# Arduino_Nano_Countdown_Timer_7-seg_CC.net
KiCad netlist of a schematic drawn in EAGLE
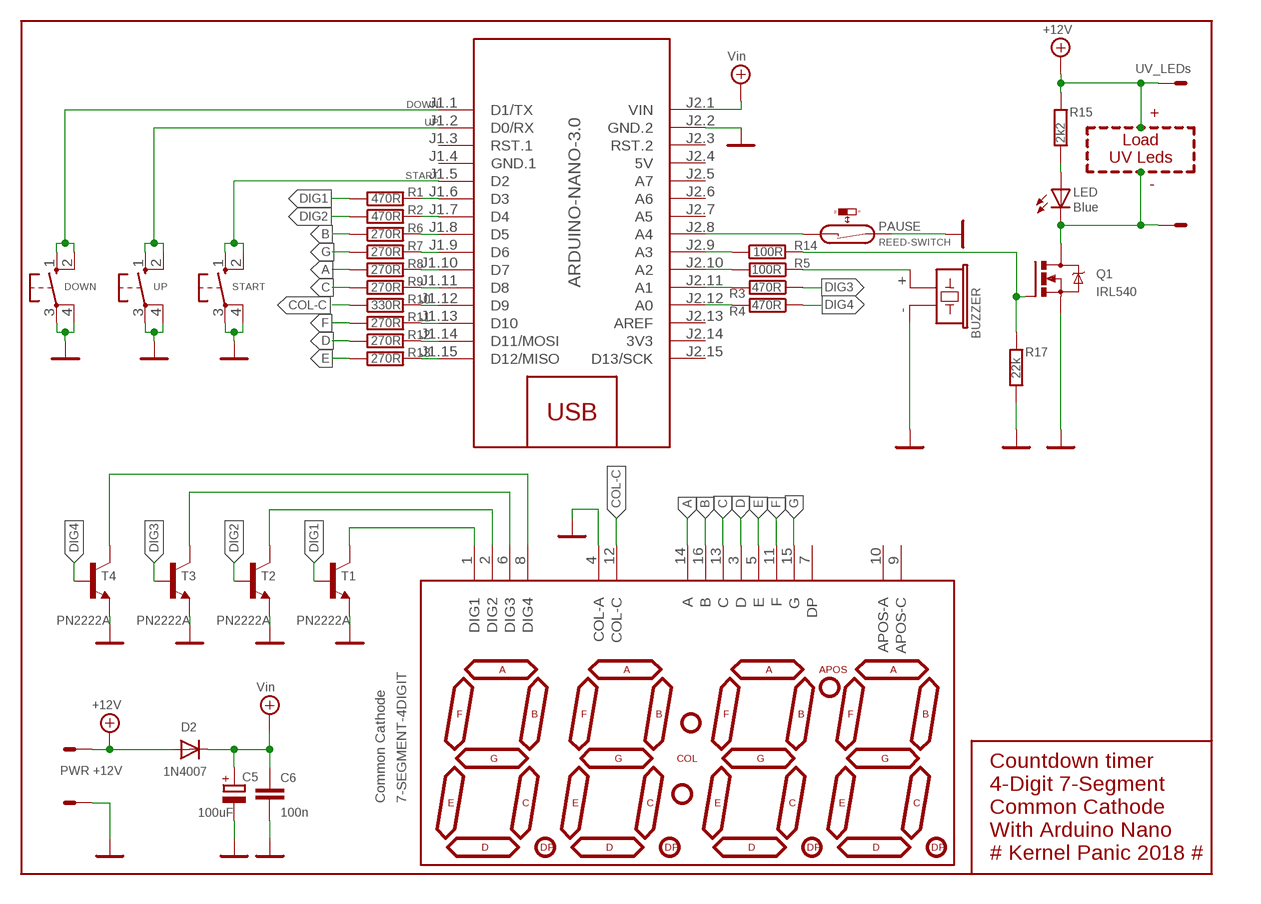
[diagram p0: schematic, sheet 1]

(export (version "E")
  (design (tool "Eeschema 10.0.6"))
  (components
    (comp (ref "BUZZER")
      (value "F/CM12P")
      (footprint "eagle-import:F_CM12P")
      (libsource (lib "eagle-import") (part "F/CM12P"))
    )
    (comp (ref "C5")
      (value "100uF")
      (footprint "eagle-import:E5-6.5")
      (libsource (lib "eagle-import") (part "CAPACITOR_POLE5-6.5"))
    )
    (comp (ref "C6")
      (value "100n")
      (footprint "eagle-import:C050-025X075")
      (libsource (lib "eagle-import") (part "CAPACITOR050-025X075"))
    )
    (comp (ref "D2")
      (value "1N4007")
      (footprint "eagle-import:DO41-10")
      (libsource (lib "eagle-import") (part "DIODE1N4004"))
    )
    (comp (ref "DOWN")
      (value "SWITCHE6K")
      (footprint "eagle-import:DTE6K")
      (libsource (lib "eagle-import") (part "SWITCHE6K"))
    )
    (comp (ref "LED")
      (value "Blue")
      (footprint "eagle-import:LED3MM")
      (libsource (lib "eagle-import") (part "LED3MM"))
    )
    (comp (ref "LED2")
      (value "7-SEGMENT-4DIGIT")
      (footprint "eagle-import:7-SEGMENT-4DIGIT")
      (libsource (lib "eagle-import") (part "7-SEGMENT-4DIGIT"))
    )
    (comp (ref "LOAD")
      (value "UV_LEDs")
      (footprint "eagle-import:22-23-2021")
      (fields (field (name "MF") "MOLEX") (field (name "MPN") "22-23-2021"))
      (libsource (lib "eagle-import") (part "22-23-2021"))
    )
    (comp (ref "M2")
      (value "ARDUINO-NANO-3.0")
      (footprint "eagle-import:ARDUINO-NANO-3.0")
      (libsource (lib "eagle-import") (part "ARDUINO-NANO-3.0"))
    )
    (comp (ref "PAUSE")
      (value "REED-SWITCH")
      (footprint "eagle-import:2PIN_HEADER")
      (libsource (lib "eagle-import") (part "REED-SWITCH-2PIN"))
    )
    (comp (ref "PWR")
      (value "PWR +12V")
      (footprint "eagle-import:22-23-2021")
      (fields (field (name "MF") "MOLEX") (field (name "MPN") "22-23-2021"))
      (libsource (lib "eagle-import") (part "22-23-2021"))
    )
    (comp (ref "Q1")
      (value "IRL540")
      (footprint "eagle-import:TO220BV")
      (libsource (lib "eagle-import") (part "IRF540"))
    )
    (comp (ref "R1")
      (value "470R")
      (footprint "eagle-import:R0805")
      (libsource (lib "eagle-import") (part "RESISTORR0805"))
    )
    (comp (ref "R2")
      (value "470R")
      (footprint "eagle-import:R0805")
      (libsource (lib "eagle-import") (part "RESISTORR0805"))
    )
    (comp (ref "R3")
      (value "470R")
      (footprint "eagle-import:R0805")
      (libsource (lib "eagle-import") (part "RESISTORR0805"))
    )
    (comp (ref "R4")
      (value "470R")
      (footprint "eagle-import:R0805")
      (libsource (lib "eagle-import") (part "RESISTORR0805"))
    )
    (comp (ref "R5")
      (value "100R")
      (footprint "eagle-import:R0805")
      (libsource (lib "eagle-import") (part "RESISTORR0805"))
    )
    (comp (ref "R6")
      (value "270R")
      (footprint "eagle-import:R0805")
      (libsource (lib "eagle-import") (part "RESISTORR0805"))
    )
    (comp (ref "R7")
      (value "270R")
      (footprint "eagle-import:R0805")
      (libsource (lib "eagle-import") (part "RESISTORR0805"))
    )
    (comp (ref "R8")
      (value "270R")
      (footprint "eagle-import:R0805")
      (libsource (lib "eagle-import") (part "RESISTORR0805"))
    )
    (comp (ref "R9")
      (value "270R")
      (footprint "eagle-import:R0805")
      (libsource (lib "eagle-import") (part "RESISTORR0805"))
    )
    (comp (ref "R10")
      (value "330R")
      (footprint "eagle-import:R0805")
      (libsource (lib "eagle-import") (part "RESISTORR0805"))
    )
    (comp (ref "R11")
      (value "270R")
      (footprint "eagle-import:R0805")
      (libsource (lib "eagle-import") (part "RESISTORR0805"))
    )
    (comp (ref "R12")
      (value "270R")
      (footprint "eagle-import:R0805")
      (libsource (lib "eagle-import") (part "RESISTORR0805"))
    )
    (comp (ref "R13")
      (value "270R")
      (footprint "eagle-import:R0805")
      (libsource (lib "eagle-import") (part "RESISTORR0805"))
    )
    (comp (ref "R14")
      (value "100R")
      (footprint "eagle-import:0207_10-8")
      (libsource (lib "eagle-import") (part "RESISTOR0207/10-OCTAGON"))
    )
    (comp (ref "R15")
      (value "2k2")
      (footprint "eagle-import:R0805")
      (libsource (lib "eagle-import") (part "RESISTORR0805"))
    )
    (comp (ref "R17")
      (value "22k")
      (footprint "eagle-import:R0805")
      (libsource (lib "eagle-import") (part "RESISTORR0805"))
    )
    (comp (ref "START")
      (value "SWITCHE6K")
      (footprint "eagle-import:DTE6K")
      (libsource (lib "eagle-import") (part "SWITCHE6K"))
    )
    (comp (ref "T1")
      (value "PN2222A")
      (footprint "eagle-import:TO92-EBC-OVAL")
      (libsource (lib "eagle-import") (part "2N2222"))
    )
    (comp (ref "T2")
      (value "PN2222A")
      (footprint "eagle-import:TO92-EBC-OVAL")
      (libsource (lib "eagle-import") (part "2N2222"))
    )
    (comp (ref "T3")
      (value "PN2222A")
      (footprint "eagle-import:TO92-EBC-OVAL")
      (libsource (lib "eagle-import") (part "2N2222"))
    )
    (comp (ref "T4")
      (value "PN2222A")
      (footprint "eagle-import:TO92-EBC-OVAL")
      (libsource (lib "eagle-import") (part "2N2222"))
    )
    (comp (ref "UP")
      (value "SWITCHE6K")
      (footprint "eagle-import:DTE6K")
      (libsource (lib "eagle-import") (part "SWITCHE6K"))
    )
  )
  (nets
    (net (code "1") (name "+12V") (class "Default")
      (node (ref "D2") (pin "A") (pinfunction "A_A") (pintype "passive"))
      (node (ref "LOAD") (pin "1") (pinfunction "S_1") (pintype "passive"))
      (node (ref "PWR") (pin "2") (pinfunction "S_2") (pintype "passive"))
      (node (ref "R15") (pin "1") (pinfunction "1_1") (pintype "passive"))
    )
    (net (code "2") (name "/3V3") (class "Default")
      (node (ref "M2") (pin "J2.14") (pinfunction "3V3_J2.14") (pintype "power_in"))
    )
    (net (code "3") (name "/5V") (class "Default")
      (node (ref "M2") (pin "J2.4") (pinfunction "5V_J2.4") (pintype "power_in"))
    )
    (net (code "4") (name "/DOWN") (class "Default")
      (node (ref "DOWN") (pin "1") (pinfunction "S_1") (pintype "passive"))
      (node (ref "DOWN") (pin "2") (pinfunction "S_2") (pintype "passive"))
      (node (ref "M2") (pin "J1.1") (pinfunction "D1/TX_J1.1") (pintype "bidirectional"))
    )
    (net (code "5") (name "/GND.1") (class "Default")
      (node (ref "M2") (pin "J1.4") (pinfunction "GND.1_J1.4") (pintype "power_in"))
    )
    (net (code "6") (name "/START") (class "Default")
      (node (ref "M2") (pin "J1.5") (pinfunction "D2_J1.5") (pintype "bidirectional"))
      (node (ref "START") (pin "1") (pinfunction "S_1") (pintype "passive"))
      (node (ref "START") (pin "2") (pinfunction "S_2") (pintype "passive"))
    )
    (net (code "7") (name "/UP") (class "Default")
      (node (ref "M2") (pin "J1.2") (pinfunction "D0/RX_J1.2") (pintype "bidirectional"))
      (node (ref "UP") (pin "1") (pinfunction "S_1") (pintype "passive"))
      (node (ref "UP") (pin "2") (pinfunction "S_2") (pintype "passive"))
    )
    (net (code "8") (name "A") (class "Default")
      (node (ref "LED2") (pin "14") (pinfunction "A_14") (pintype "bidirectional"))
      (node (ref "R8") (pin "1") (pinfunction "1_1") (pintype "passive"))
    )
    (net (code "9") (name "B") (class "Default")
      (node (ref "LED2") (pin "16") (pinfunction "B_16") (pintype "bidirectional"))
      (node (ref "R6") (pin "1") (pinfunction "1_1") (pintype "passive"))
    )
    (net (code "10") (name "C") (class "Default")
      (node (ref "LED2") (pin "13") (pinfunction "C_13") (pintype "bidirectional"))
      (node (ref "R9") (pin "1") (pinfunction "1_1") (pintype "passive"))
    )
    (net (code "11") (name "COL-C") (class "Default")
      (node (ref "LED2") (pin "12") (pinfunction "COL-C_12") (pintype "bidirectional"))
      (node (ref "R10") (pin "1") (pinfunction "1_1") (pintype "passive"))
    )
    (net (code "12") (name "D") (class "Default")
      (node (ref "LED2") (pin "3") (pinfunction "D_3") (pintype "bidirectional"))
      (node (ref "R12") (pin "1") (pinfunction "1_1") (pintype "passive"))
    )
    (net (code "13") (name "DIG1") (class "Default")
      (node (ref "R1") (pin "1") (pinfunction "1_1") (pintype "passive"))
      (node (ref "T1") (pin "B") (pinfunction "B_B") (pintype "passive"))
    )
    (net (code "14") (name "DIG2") (class "Default")
      (node (ref "R2") (pin "1") (pinfunction "1_1") (pintype "passive"))
      (node (ref "T2") (pin "B") (pinfunction "B_B") (pintype "passive"))
    )
    (net (code "15") (name "DIG3") (class "Default")
      (node (ref "R3") (pin "1") (pinfunction "1_1") (pintype "passive"))
      (node (ref "T3") (pin "B") (pinfunction "B_B") (pintype "passive"))
    )
    (net (code "16") (name "DIG4") (class "Default")
      (node (ref "R4") (pin "1") (pinfunction "1_1") (pintype "passive"))
      (node (ref "T4") (pin "B") (pinfunction "B_B") (pintype "passive"))
    )
    (net (code "17") (name "E") (class "Default")
      (node (ref "LED2") (pin "5") (pinfunction "E_5") (pintype "bidirectional"))
      (node (ref "R13") (pin "1") (pinfunction "1_1") (pintype "passive"))
    )
    (net (code "18") (name "F") (class "Default")
      (node (ref "LED2") (pin "11") (pinfunction "F_11") (pintype "bidirectional"))
      (node (ref "R11") (pin "1") (pinfunction "1_1") (pintype "passive"))
    )
    (net (code "19") (name "G") (class "Default")
      (node (ref "LED2") (pin "15") (pinfunction "G_15") (pintype "bidirectional"))
      (node (ref "R7") (pin "1") (pinfunction "1_1") (pintype "passive"))
    )
    (net (code "20") (name "GND") (class "Default")
      (node (ref "BUZZER") (pin "-") (pinfunction "2_-") (pintype "passive"))
      (node (ref "C5") (pin "-") (pinfunction "-_-") (pintype "passive"))
      (node (ref "C6") (pin "2") (pinfunction "2_2") (pintype "passive"))
      (node (ref "DOWN") (pin "3") (pinfunction "P_3") (pintype "passive"))
      (node (ref "DOWN") (pin "4") (pinfunction "P_4") (pintype "passive"))
      (node (ref "LED2") (pin "4") (pinfunction "COL-A_4") (pintype "bidirectional"))
      (node (ref "M2") (pin "J2.2") (pinfunction "GND.2_J2.2") (pintype "power_in"))
      (node (ref "PAUSE") (pin "2") (pinfunction "2_2") (pintype "passive"))
      (node (ref "PWR") (pin "1") (pinfunction "S_1") (pintype "passive"))
      (node (ref "Q1") (pin "S") (pinfunction "S_S") (pintype "passive"))
      (node (ref "R17") (pin "2") (pinfunction "2_2") (pintype "passive"))
      (node (ref "START") (pin "3") (pinfunction "P_3") (pintype "passive"))
      (node (ref "START") (pin "4") (pinfunction "P_4") (pintype "passive"))
      (node (ref "T1") (pin "E") (pinfunction "E_E") (pintype "passive"))
      (node (ref "T2") (pin "E") (pinfunction "E_E") (pintype "passive"))
      (node (ref "T3") (pin "E") (pinfunction "E_E") (pintype "passive"))
      (node (ref "T4") (pin "E") (pinfunction "E_E") (pintype "passive"))
      (node (ref "UP") (pin "3") (pinfunction "P_3") (pintype "passive"))
      (node (ref "UP") (pin "4") (pinfunction "P_4") (pintype "passive"))
    )
    (net (code "21") (name "Net-(BUZZER-1)") (class "Default")
      (node (ref "BUZZER") (pin "+") (pinfunction "1_+") (pintype "passive"))
      (node (ref "R5") (pin "1") (pinfunction "1_1") (pintype "passive"))
    )
    (net (code "22") (name "Net-(LED-C)") (class "Default")
      (node (ref "LED") (pin "K") (pinfunction "C_K") (pintype "passive"))
      (node (ref "LOAD") (pin "2") (pinfunction "S_2") (pintype "passive"))
      (node (ref "Q1") (pin "D") (pinfunction "D_D") (pintype "passive"))
    )
    (net (code "23") (name "Net-(LED-PadA)") (class "Default")
      (node (ref "LED") (pin "A") (pinfunction "A_A") (pintype "passive"))
      (node (ref "R15") (pin "2") (pinfunction "2_2") (pintype "passive"))
    )
    (net (code "24") (name "Net-(LED2-DIG1)") (class "Default")
      (node (ref "LED2") (pin "1") (pinfunction "DIG1_1") (pintype "bidirectional"))
      (node (ref "T1") (pin "C") (pinfunction "C_C") (pintype "passive"))
    )
    (net (code "25") (name "Net-(LED2-DIG2)") (class "Default")
      (node (ref "LED2") (pin "2") (pinfunction "DIG2_2") (pintype "bidirectional"))
      (node (ref "T2") (pin "C") (pinfunction "C_C") (pintype "passive"))
    )
    (net (code "26") (name "Net-(LED2-DIG3)") (class "Default")
      (node (ref "LED2") (pin "6") (pinfunction "DIG3_6") (pintype "bidirectional"))
      (node (ref "T3") (pin "C") (pinfunction "C_C") (pintype "passive"))
    )
    (net (code "27") (name "Net-(LED2-DIG4)") (class "Default")
      (node (ref "LED2") (pin "8") (pinfunction "DIG4_8") (pintype "bidirectional"))
      (node (ref "T4") (pin "C") (pinfunction "C_C") (pintype "passive"))
    )
    (net (code "28") (name "Net-(M2-A0)") (class "Default")
      (node (ref "M2") (pin "J2.12") (pinfunction "A0_J2.12") (pintype "bidirectional"))
      (node (ref "R4") (pin "2") (pinfunction "2_2") (pintype "passive"))
    )
    (net (code "29") (name "Net-(M2-A1)") (class "Default")
      (node (ref "M2") (pin "J2.11") (pinfunction "A1_J2.11") (pintype "bidirectional"))
      (node (ref "R3") (pin "2") (pinfunction "2_2") (pintype "passive"))
    )
    (net (code "30") (name "Net-(M2-A2)") (class "Default")
      (node (ref "M2") (pin "J2.10") (pinfunction "A2_J2.10") (pintype "bidirectional"))
      (node (ref "R5") (pin "2") (pinfunction "2_2") (pintype "passive"))
    )
    (net (code "31") (name "Net-(M2-A3)") (class "Default")
      (node (ref "M2") (pin "J2.9") (pinfunction "A3_J2.9") (pintype "bidirectional"))
      (node (ref "R14") (pin "1") (pinfunction "1_1") (pintype "passive"))
    )
    (net (code "32") (name "Net-(M2-A4)") (class "Default")
      (node (ref "M2") (pin "J2.8") (pinfunction "A4_J2.8") (pintype "bidirectional"))
      (node (ref "PAUSE") (pin "1") (pinfunction "1_1") (pintype "passive"))
    )
    (net (code "33") (name "Net-(M2-D3)") (class "Default")
      (node (ref "M2") (pin "J1.6") (pinfunction "D3_J1.6") (pintype "bidirectional"))
      (node (ref "R1") (pin "2") (pinfunction "2_2") (pintype "passive"))
    )
    (net (code "34") (name "Net-(M2-D4)") (class "Default")
      (node (ref "M2") (pin "J1.7") (pinfunction "D4_J1.7") (pintype "bidirectional"))
      (node (ref "R2") (pin "2") (pinfunction "2_2") (pintype "passive"))
    )
    (net (code "35") (name "Net-(M2-D5)") (class "Default")
      (node (ref "M2") (pin "J1.8") (pinfunction "D5_J1.8") (pintype "bidirectional"))
      (node (ref "R6") (pin "2") (pinfunction "2_2") (pintype "passive"))
    )
    (net (code "36") (name "Net-(M2-D6)") (class "Default")
      (node (ref "M2") (pin "J1.9") (pinfunction "D6_J1.9") (pintype "bidirectional"))
      (node (ref "R7") (pin "2") (pinfunction "2_2") (pintype "passive"))
    )
    (net (code "37") (name "Net-(M2-D7)") (class "Default")
      (node (ref "M2") (pin "J1.10") (pinfunction "D7_J1.10") (pintype "bidirectional"))
      (node (ref "R8") (pin "2") (pinfunction "2_2") (pintype "passive"))
    )
    (net (code "38") (name "Net-(M2-D8)") (class "Default")
      (node (ref "M2") (pin "J1.11") (pinfunction "D8_J1.11") (pintype "bidirectional"))
      (node (ref "R9") (pin "2") (pinfunction "2_2") (pintype "passive"))
    )
    (net (code "39") (name "Net-(M2-D9)") (class "Default")
      (node (ref "M2") (pin "J1.12") (pinfunction "D9_J1.12") (pintype "bidirectional"))
      (node (ref "R10") (pin "2") (pinfunction "2_2") (pintype "passive"))
    )
    (net (code "40") (name "Net-(M2-D10)") (class "Default")
      (node (ref "M2") (pin "J1.13") (pinfunction "D10_J1.13") (pintype "bidirectional"))
      (node (ref "R11") (pin "2") (pinfunction "2_2") (pintype "passive"))
    )
    (net (code "41") (name "Net-(M2-D11{slash}MOSI)") (class "Default")
      (node (ref "M2") (pin "J1.14") (pinfunction "D11/MOSI_J1.14") (pintype "bidirectional"))
      (node (ref "R12") (pin "2") (pinfunction "2_2") (pintype "passive"))
    )
    (net (code "42") (name "Net-(M2-D12{slash}MISO)") (class "Default")
      (node (ref "M2") (pin "J1.15") (pinfunction "D12/MISO_J1.15") (pintype "bidirectional"))
      (node (ref "R13") (pin "2") (pinfunction "2_2") (pintype "passive"))
    )
    (net (code "43") (name "Net-(Q1-PadG)") (class "Default")
      (node (ref "Q1") (pin "G") (pinfunction "G_G") (pintype "passive"))
      (node (ref "R14") (pin "2") (pinfunction "2_2") (pintype "passive"))
      (node (ref "R17") (pin "1") (pinfunction "1_1") (pintype "passive"))
    )
    (net (code "44") (name "Vin") (class "Default")
      (node (ref "C5") (pin "+") (pinfunction "+_+") (pintype "passive"))
      (node (ref "C6") (pin "1") (pinfunction "1_1") (pintype "passive"))
      (node (ref "D2") (pin "C") (pinfunction "C_C") (pintype "passive"))
      (node (ref "M2") (pin "J2.1") (pinfunction "VIN_J2.1") (pintype "power_in"))
    )
    (net (code "45") (name "unconnected-(LED2-APOS-A-Pad10)") (class "Default")
      (node (ref "LED2") (pin "10") (pinfunction "APOS-A_10") (pintype "bidirectional"))
    )
    (net (code "46") (name "unconnected-(LED2-APOS-C-Pad9)") (class "Default")
      (node (ref "LED2") (pin "9") (pinfunction "APOS-C_9") (pintype "bidirectional"))
    )
    (net (code "47") (name "unconnected-(LED2-DP-Pad7)") (class "Default")
      (node (ref "LED2") (pin "7") (pinfunction "DP_7") (pintype "bidirectional"))
    )
    (net (code "48") (name "unconnected-(M2-A5-PadJ2.7)") (class "Default")
      (node (ref "M2") (pin "J2.7") (pinfunction "A5_J2.7") (pintype "bidirectional"))
    )
    (net (code "49") (name "unconnected-(M2-A6-PadJ2.6)") (class "Default")
      (node (ref "M2") (pin "J2.6") (pinfunction "A6_J2.6") (pintype "bidirectional"))
    )
    (net (code "50") (name "unconnected-(M2-A7-PadJ2.5)") (class "Default")
      (node (ref "M2") (pin "J2.5") (pinfunction "A7_J2.5") (pintype "bidirectional"))
    )
    (net (code "51") (name "unconnected-(M2-AREF-PadJ2.13)") (class "Default")
      (node (ref "M2") (pin "J2.13") (pinfunction "AREF_J2.13") (pintype "bidirectional"))
    )
    (net (code "52") (name "unconnected-(M2-D13{slash}SCK-PadJ2.15)") (class "Default")
      (node (ref "M2") (pin "J2.15") (pinfunction "D13/SCK_J2.15") (pintype "bidirectional"))
    )
    (net (code "53") (name "unconnected-(M2-RST.1-PadJ1.3)") (class "Default")
      (node (ref "M2") (pin "J1.3") (pinfunction "RST.1_J1.3") (pintype "bidirectional"))
    )
    (net (code "54") (name "unconnected-(M2-RST.2-PadJ2.3)") (class "Default")
      (node (ref "M2") (pin "J2.3") (pinfunction "RST.2_J2.3") (pintype "bidirectional"))
    )
  )
)
